# esp-tree.net
KiCad netlist of a schematic drawn in EAGLE
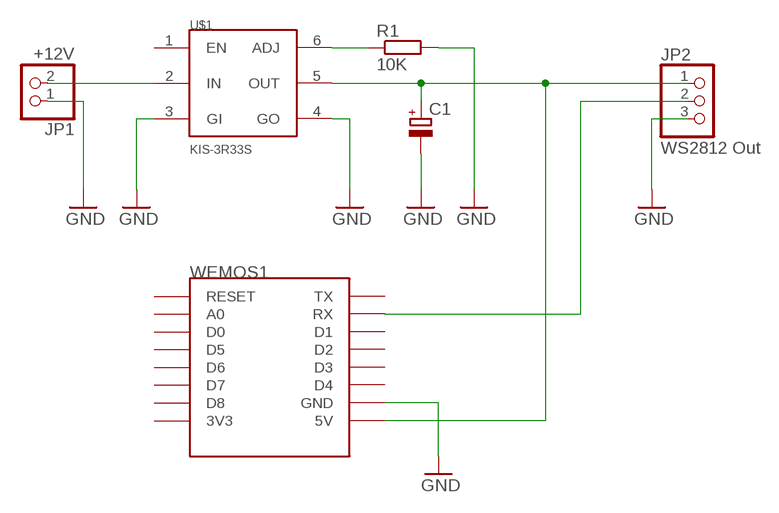
[diagram p0: schematic, sheet 1]

(export (version "E")
  (design (tool "Eeschema 10.0.6"))
  (components
    (comp (ref "C1")
      (value "CPOL-EUB45181B")
      (footprint "eagle-import:B45181B")
      (libsource (lib "eagle-import") (part "CPOL-EUB45181B"))
    )
    (comp (ref "JP1")
      (value "+12V")
      (footprint "eagle-import:1X02")
      (libsource (lib "eagle-import") (part "PINHD-1X2"))
    )
    (comp (ref "JP2")
      (value "WS2812 Out")
      (footprint "eagle-import:1X03")
      (libsource (lib "eagle-import") (part "PINHD-1X3"))
    )
    (comp (ref "R1")
      (value "10K")
      (footprint "eagle-import:0204_5")
      (libsource (lib "eagle-import") (part "R-EU_0204/5"))
    )
    (comp (ref "U$1")
      (value "KIS-3R33S")
      (footprint "eagle-import:KIS-3R33S")
      (libsource (lib "eagle-import") (part "KIS-3R33S"))
    )
    (comp (ref "WEMOS1")
      (value "WEMOS-D1-MINI")
      (footprint "eagle-import:WEMOS-D1-MINI")
      (libsource (lib "eagle-import") (part "WEMOS-D1-MINI"))
    )
  )
  (nets
    (net (code "1") (name "GND") (class "Default")
      (node (ref "C1") (pin "-") (pinfunction "-_-") (pintype "passive"))
      (node (ref "JP1") (pin "1") (pinfunction "1_1") (pintype "passive"))
      (node (ref "JP2") (pin "3") (pinfunction "3_3") (pintype "passive"))
      (node (ref "R1") (pin "2") (pinfunction "2_2") (pintype "passive"))
      (node (ref "U$1") (pin "3") (pinfunction "GI_3") (pintype "power_in"))
      (node (ref "U$1") (pin "4") (pinfunction "GO_4") (pintype "power_in"))
      (node (ref "WEMOS1") (pin "GND") (pinfunction "GND_GND") (pintype "bidirectional"))
    )
    (net (code "2") (name "Net-(JP2-Pad2)") (class "Default")
      (node (ref "JP2") (pin "2") (pinfunction "2_2") (pintype "passive"))
      (node (ref "WEMOS1") (pin "RX") (pinfunction "RX_RX") (pintype "bidirectional"))
    )
    (net (code "3") (name "Net-(U$1-ADJ)") (class "Default")
      (node (ref "R1") (pin "1") (pinfunction "1_1") (pintype "passive"))
      (node (ref "U$1") (pin "6") (pinfunction "ADJ_6") (pintype "bidirectional"))
    )
    (net (code "4") (name "Net-(U$1-IN)") (class "Default")
      (node (ref "JP1") (pin "2") (pinfunction "2_2") (pintype "passive"))
      (node (ref "U$1") (pin "2") (pinfunction "IN_2") (pintype "bidirectional"))
    )
    (net (code "5") (name "Net-(U$1-OUT)") (class "Default")
      (node (ref "C1") (pin "+") (pinfunction "+_+") (pintype "passive"))
      (node (ref "JP2") (pin "1") (pinfunction "1_1") (pintype "passive"))
      (node (ref "U$1") (pin "5") (pinfunction "OUT_5") (pintype "bidirectional"))
      (node (ref "WEMOS1") (pin "5V") (pinfunction "5V_5V") (pintype "bidirectional"))
    )
    (net (code "6") (name "unconnected-(U$1-EN-Pad1)") (class "Default")
      (node (ref "U$1") (pin "1") (pinfunction "EN_1") (pintype "bidirectional"))
    )
    (net (code "7") (name "unconnected-(WEMOS1-Pad3V3)") (class "Default")
      (node (ref "WEMOS1") (pin "3V3") (pinfunction "3V3_3V3") (pintype "bidirectional"))
    )
    (net (code "8") (name "unconnected-(WEMOS1-PadA0)") (class "Default")
      (node (ref "WEMOS1") (pin "A0") (pinfunction "A0_A0") (pintype "bidirectional"))
    )
    (net (code "9") (name "unconnected-(WEMOS1-PadD0)") (class "Default")
      (node (ref "WEMOS1") (pin "D0") (pinfunction "D0_D0") (pintype "bidirectional"))
    )
    (net (code "10") (name "unconnected-(WEMOS1-PadD1)") (class "Default")
      (node (ref "WEMOS1") (pin "D1") (pinfunction "D1_D1") (pintype "bidirectional"))
    )
    (net (code "11") (name "unconnected-(WEMOS1-PadD2)") (class "Default")
      (node (ref "WEMOS1") (pin "D2") (pinfunction "D2_D2") (pintype "bidirectional"))
    )
    (net (code "12") (name "unconnected-(WEMOS1-PadD3)") (class "Default")
      (node (ref "WEMOS1") (pin "D3") (pinfunction "D3_D3") (pintype "bidirectional"))
    )
    (net (code "13") (name "unconnected-(WEMOS1-PadD4)") (class "Default")
      (node (ref "WEMOS1") (pin "D4") (pinfunction "D4_D4") (pintype "bidirectional"))
    )
    (net (code "14") (name "unconnected-(WEMOS1-PadD5)") (class "Default")
      (node (ref "WEMOS1") (pin "D5") (pinfunction "D5_D5") (pintype "bidirectional"))
    )
    (net (code "15") (name "unconnected-(WEMOS1-PadD6)") (class "Default")
      (node (ref "WEMOS1") (pin "D6") (pinfunction "D6_D6") (pintype "bidirectional"))
    )
    (net (code "16") (name "unconnected-(WEMOS1-PadD7)") (class "Default")
      (node (ref "WEMOS1") (pin "D7") (pinfunction "D7_D7") (pintype "bidirectional"))
    )
    (net (code "17") (name "unconnected-(WEMOS1-PadD8)") (class "Default")
      (node (ref "WEMOS1") (pin "D8") (pinfunction "D8_D8") (pintype "bidirectional"))
    )
    (net (code "18") (name "unconnected-(WEMOS1-PadRESET)") (class "Default")
      (node (ref "WEMOS1") (pin "RESET") (pinfunction "RESET_RESET") (pintype "bidirectional"))
    )
    (net (code "19") (name "unconnected-(WEMOS1-PadTX)") (class "Default")
      (node (ref "WEMOS1") (pin "TX") (pinfunction "TX_TX") (pintype "bidirectional"))
    )
  )
)
